# M207C.net
KiCad netlist of a schematic drawn in EAGLE
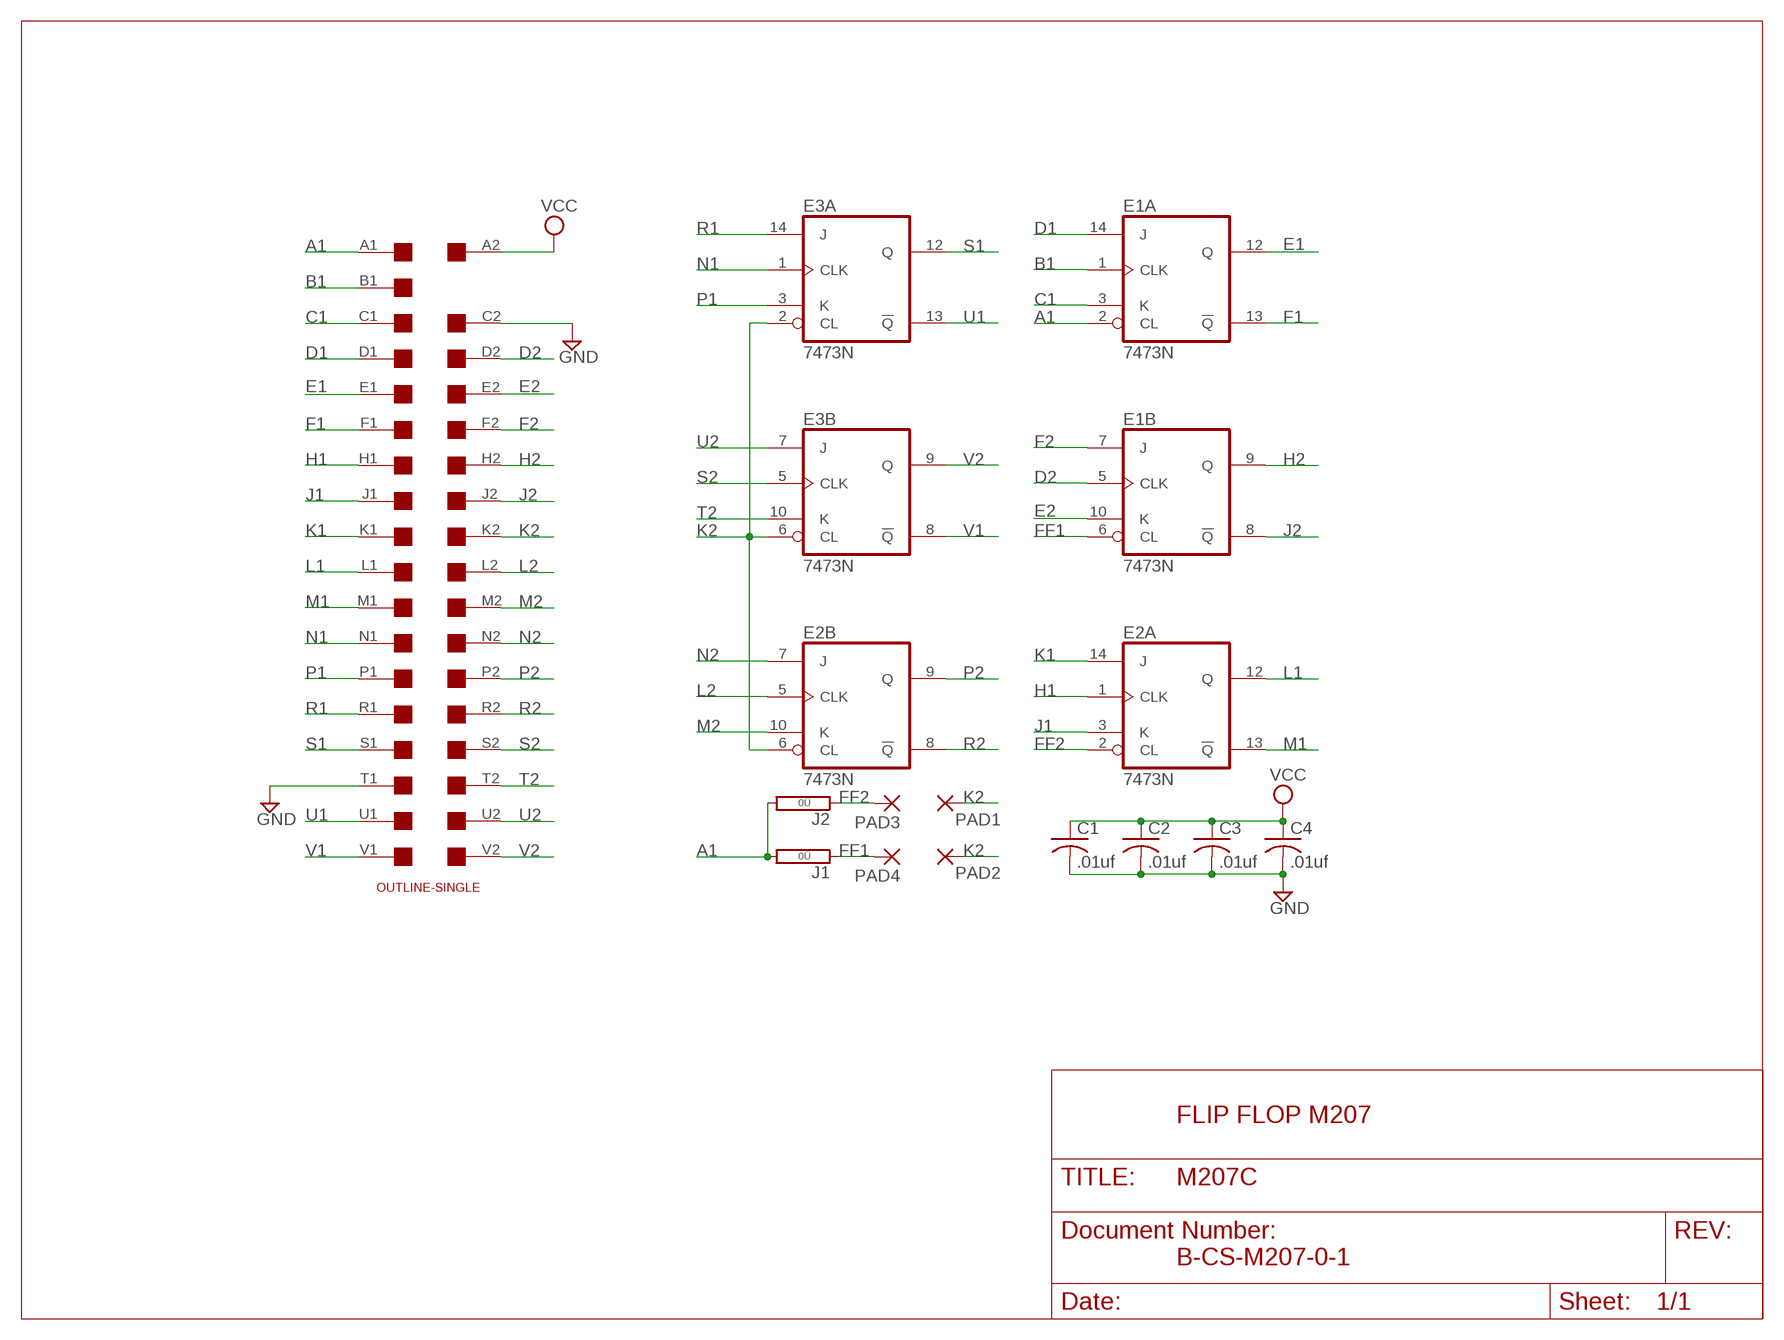
[diagram p0: schematic, sheet 1]

(export (version "E")
  (design (tool "Eeschema 10.0.6"))
  (components
    (comp (ref "C1")
      (value ".01uf")
      (footprint "eagle-import:C050-025X075")
      (libsource (lib "eagle-import") (part "C-US050-025X075"))
    )
    (comp (ref "C2")
      (value ".01uf")
      (footprint "eagle-import:C050-025X075")
      (libsource (lib "eagle-import") (part "C-US050-025X075"))
    )
    (comp (ref "C3")
      (value ".01uf")
      (footprint "eagle-import:C050-025X075")
      (libsource (lib "eagle-import") (part "C-US050-025X075"))
    )
    (comp (ref "C4")
      (value ".01uf")
      (footprint "eagle-import:C050-025X075")
      (libsource (lib "eagle-import") (part "C-US050-025X075"))
    )
    (comp (ref "E1")
      (value "7473N")
      (footprint "eagle-import:DIL14")
      (libsource (lib "eagle-import") (part "7473NLS"))
    )
    (comp (ref "E2")
      (value "7473N")
      (footprint "eagle-import:DIL14")
      (libsource (lib "eagle-import") (part "7473NLS"))
    )
    (comp (ref "E3")
      (value "7473N")
      (footprint "eagle-import:DIL14")
      (libsource (lib "eagle-import") (part "7473NLS"))
    )
    (comp (ref "J1")
      (value "0R")
      (footprint "eagle-import:0R_10")
      (libsource (lib "eagle-import") (part "0R"))
    )
    (comp (ref "J2")
      (value "0R")
      (footprint "eagle-import:0R_10")
      (libsource (lib "eagle-import") (part "0R"))
    )
    (comp (ref "PAD1")
      (value "1,6/0,8")
      (footprint "eagle-import:1,6_0,8")
      (libsource (lib "eagle-import") (part "1,6/0,8"))
    )
    (comp (ref "PAD2")
      (value "1,6/0,8")
      (footprint "eagle-import:1,6_0,8")
      (libsource (lib "eagle-import") (part "1,6/0,8"))
    )
    (comp (ref "PAD3")
      (value "1,6/0,8")
      (footprint "eagle-import:1,6_0,8")
      (libsource (lib "eagle-import") (part "1,6/0,8"))
    )
    (comp (ref "PAD4")
      (value "1,6/0,8")
      (footprint "eagle-import:1,6_0,8")
      (libsource (lib "eagle-import") (part "1,6/0,8"))
    )
    (comp (ref "U$1")
      (value "SINGLE")
      (footprint "eagle-import:EDGE-CON2")
      (libsource (lib "eagle-import") (part "SINGLE"))
    )
    (comp (ref "U$4")
      (value "OUTLINE-SINGLE")
      (footprint "eagle-import:SINGLE")
      (libsource (lib "eagle-import") (part "OUTLINE-SINGLE"))
    )
  )
  (nets
    (net (code "1") (name "/A1") (class "Default")
      (node (ref "E1") (pin "2") (pinfunction "CL_2") (pintype "input"))
      (node (ref "J1") (pin "2") (pinfunction "2_2") (pintype "passive"))
      (node (ref "J2") (pin "2") (pinfunction "2_2") (pintype "passive"))
      (node (ref "U$1") (pin "A1") (pinfunction "1_A1") (pintype "bidirectional"))
    )
    (net (code "2") (name "/B1") (class "Default")
      (node (ref "E1") (pin "1") (pinfunction "CLK_1") (pintype "input"))
      (node (ref "U$1") (pin "B1") (pinfunction "1_B1") (pintype "bidirectional"))
    )
    (net (code "3") (name "/C1") (class "Default")
      (node (ref "E1") (pin "3") (pinfunction "K_3") (pintype "input"))
      (node (ref "U$1") (pin "C1") (pinfunction "1_C1") (pintype "bidirectional"))
    )
    (net (code "4") (name "/D1") (class "Default")
      (node (ref "E1") (pin "14") (pinfunction "J_14") (pintype "input"))
      (node (ref "U$1") (pin "D1") (pinfunction "1_D1") (pintype "bidirectional"))
    )
    (net (code "5") (name "/D2") (class "Default")
      (node (ref "E1") (pin "5") (pinfunction "CLK_5") (pintype "input"))
      (node (ref "U$1") (pin "D2") (pinfunction "1_D2") (pintype "bidirectional"))
    )
    (net (code "6") (name "/E1") (class "Default")
      (node (ref "E1") (pin "12") (pinfunction "Q_12") (pintype "output"))
      (node (ref "U$1") (pin "E1") (pinfunction "1_E1") (pintype "bidirectional"))
    )
    (net (code "7") (name "/E2") (class "Default")
      (node (ref "E1") (pin "10") (pinfunction "K_10") (pintype "input"))
      (node (ref "U$1") (pin "E2") (pinfunction "1_E2") (pintype "bidirectional"))
    )
    (net (code "8") (name "/F1") (class "Default")
      (node (ref "E1") (pin "13") (pinfunction "~{Q}_13") (pintype "output"))
      (node (ref "U$1") (pin "F1") (pinfunction "1_F1") (pintype "bidirectional"))
    )
    (net (code "9") (name "/F2") (class "Default")
      (node (ref "E1") (pin "7") (pinfunction "J_7") (pintype "input"))
      (node (ref "U$1") (pin "F2") (pinfunction "1_F2") (pintype "bidirectional"))
    )
    (net (code "10") (name "/FF1") (class "Default")
      (node (ref "E1") (pin "6") (pinfunction "CL_6") (pintype "input"))
      (node (ref "J1") (pin "1") (pinfunction "1_1") (pintype "passive"))
      (node (ref "PAD4") (pin "1") (pinfunction "P_1") (pintype "passive"))
    )
    (net (code "11") (name "/FF2") (class "Default")
      (node (ref "E2") (pin "2") (pinfunction "CL_2") (pintype "input"))
      (node (ref "J2") (pin "1") (pinfunction "1_1") (pintype "passive"))
      (node (ref "PAD3") (pin "1") (pinfunction "P_1") (pintype "passive"))
    )
    (net (code "12") (name "/H1") (class "Default")
      (node (ref "E2") (pin "1") (pinfunction "CLK_1") (pintype "input"))
      (node (ref "U$1") (pin "H1") (pinfunction "1_H1") (pintype "bidirectional"))
    )
    (net (code "13") (name "/H2") (class "Default")
      (node (ref "E1") (pin "9") (pinfunction "Q_9") (pintype "output"))
      (node (ref "U$1") (pin "H2") (pinfunction "1_H2") (pintype "bidirectional"))
    )
    (net (code "14") (name "/J1") (class "Default")
      (node (ref "E2") (pin "3") (pinfunction "K_3") (pintype "input"))
      (node (ref "U$1") (pin "J1") (pinfunction "1_J1") (pintype "bidirectional"))
    )
    (net (code "15") (name "/J2") (class "Default")
      (node (ref "E1") (pin "8") (pinfunction "~{Q}_8") (pintype "output"))
      (node (ref "U$1") (pin "J2") (pinfunction "1_J2") (pintype "bidirectional"))
    )
    (net (code "16") (name "/K1") (class "Default")
      (node (ref "E2") (pin "14") (pinfunction "J_14") (pintype "input"))
      (node (ref "U$1") (pin "K1") (pinfunction "1_K1") (pintype "bidirectional"))
    )
    (net (code "17") (name "/K2") (class "Default")
      (node (ref "E2") (pin "6") (pinfunction "CL_6") (pintype "input"))
      (node (ref "E3") (pin "2") (pinfunction "CL_2") (pintype "input"))
      (node (ref "E3") (pin "6") (pinfunction "CL_6") (pintype "input"))
      (node (ref "PAD1") (pin "1") (pinfunction "P_1") (pintype "passive"))
      (node (ref "PAD2") (pin "1") (pinfunction "P_1") (pintype "passive"))
      (node (ref "U$1") (pin "K2") (pinfunction "1_K2") (pintype "bidirectional"))
    )
    (net (code "18") (name "/L1") (class "Default")
      (node (ref "E2") (pin "12") (pinfunction "Q_12") (pintype "output"))
      (node (ref "U$1") (pin "L1") (pinfunction "1_L1") (pintype "bidirectional"))
    )
    (net (code "19") (name "/L2") (class "Default")
      (node (ref "E2") (pin "5") (pinfunction "CLK_5") (pintype "input"))
      (node (ref "U$1") (pin "L2") (pinfunction "1_L2") (pintype "bidirectional"))
    )
    (net (code "20") (name "/M1") (class "Default")
      (node (ref "E2") (pin "13") (pinfunction "~{Q}_13") (pintype "output"))
      (node (ref "U$1") (pin "M1") (pinfunction "1_M1") (pintype "bidirectional"))
    )
    (net (code "21") (name "/M2") (class "Default")
      (node (ref "E2") (pin "10") (pinfunction "K_10") (pintype "input"))
      (node (ref "U$1") (pin "M2") (pinfunction "1_M2") (pintype "bidirectional"))
    )
    (net (code "22") (name "/N1") (class "Default")
      (node (ref "E3") (pin "1") (pinfunction "CLK_1") (pintype "input"))
      (node (ref "U$1") (pin "N1") (pinfunction "1_N1") (pintype "bidirectional"))
    )
    (net (code "23") (name "/N2") (class "Default")
      (node (ref "E2") (pin "7") (pinfunction "J_7") (pintype "input"))
      (node (ref "U$1") (pin "N2") (pinfunction "1_N2") (pintype "bidirectional"))
    )
    (net (code "24") (name "/P1") (class "Default")
      (node (ref "E3") (pin "3") (pinfunction "K_3") (pintype "input"))
      (node (ref "U$1") (pin "P1") (pinfunction "1_P1") (pintype "bidirectional"))
    )
    (net (code "25") (name "/P2") (class "Default")
      (node (ref "E2") (pin "9") (pinfunction "Q_9") (pintype "output"))
      (node (ref "U$1") (pin "P2") (pinfunction "1_P2") (pintype "bidirectional"))
    )
    (net (code "26") (name "/R1") (class "Default")
      (node (ref "E3") (pin "14") (pinfunction "J_14") (pintype "input"))
      (node (ref "U$1") (pin "R1") (pinfunction "1_R1") (pintype "bidirectional"))
    )
    (net (code "27") (name "/R2") (class "Default")
      (node (ref "E2") (pin "8") (pinfunction "~{Q}_8") (pintype "output"))
      (node (ref "U$1") (pin "R2") (pinfunction "1_R2") (pintype "bidirectional"))
    )
    (net (code "28") (name "/S1") (class "Default")
      (node (ref "E3") (pin "12") (pinfunction "Q_12") (pintype "output"))
      (node (ref "U$1") (pin "S1") (pinfunction "1_S1") (pintype "bidirectional"))
    )
    (net (code "29") (name "/S2") (class "Default")
      (node (ref "E3") (pin "5") (pinfunction "CLK_5") (pintype "input"))
      (node (ref "U$1") (pin "S2") (pinfunction "1_S2") (pintype "bidirectional"))
    )
    (net (code "30") (name "/T2") (class "Default")
      (node (ref "E3") (pin "10") (pinfunction "K_10") (pintype "input"))
      (node (ref "U$1") (pin "T2") (pinfunction "1_T2") (pintype "bidirectional"))
    )
    (net (code "31") (name "/U1") (class "Default")
      (node (ref "E3") (pin "13") (pinfunction "~{Q}_13") (pintype "output"))
      (node (ref "U$1") (pin "U1") (pinfunction "1_U1") (pintype "bidirectional"))
    )
    (net (code "32") (name "/U2") (class "Default")
      (node (ref "E3") (pin "7") (pinfunction "J_7") (pintype "input"))
      (node (ref "U$1") (pin "U2") (pinfunction "1_U2") (pintype "bidirectional"))
    )
    (net (code "33") (name "/V1") (class "Default")
      (node (ref "E3") (pin "8") (pinfunction "~{Q}_8") (pintype "output"))
      (node (ref "U$1") (pin "V1") (pinfunction "1_V1") (pintype "bidirectional"))
    )
    (net (code "34") (name "/V2") (class "Default")
      (node (ref "E3") (pin "9") (pinfunction "Q_9") (pintype "output"))
      (node (ref "U$1") (pin "V2") (pinfunction "1_V2") (pintype "bidirectional"))
    )
    (net (code "35") (name "GND") (class "Default")
      (node (ref "C1") (pin "2") (pinfunction "2_2") (pintype "passive"))
      (node (ref "C2") (pin "2") (pinfunction "2_2") (pintype "passive"))
      (node (ref "C3") (pin "2") (pinfunction "2_2") (pintype "passive"))
      (node (ref "C4") (pin "2") (pinfunction "2_2") (pintype "passive"))
      (node (ref "U$1") (pin "C2") (pinfunction "1_C2") (pintype "bidirectional"))
      (node (ref "U$1") (pin "T1") (pinfunction "1_T1") (pintype "bidirectional"))
    )
    (net (code "36") (name "VCC") (class "Default")
      (node (ref "C1") (pin "1") (pinfunction "1_1") (pintype "passive"))
      (node (ref "C2") (pin "1") (pinfunction "1_1") (pintype "passive"))
      (node (ref "C3") (pin "1") (pinfunction "1_1") (pintype "passive"))
      (node (ref "C4") (pin "1") (pinfunction "1_1") (pintype "passive"))
      (node (ref "U$1") (pin "A2") (pinfunction "1_A2") (pintype "bidirectional"))
    )
  )
)
